# CONN.net
KiCad netlist of a schematic drawn in Altium Designer
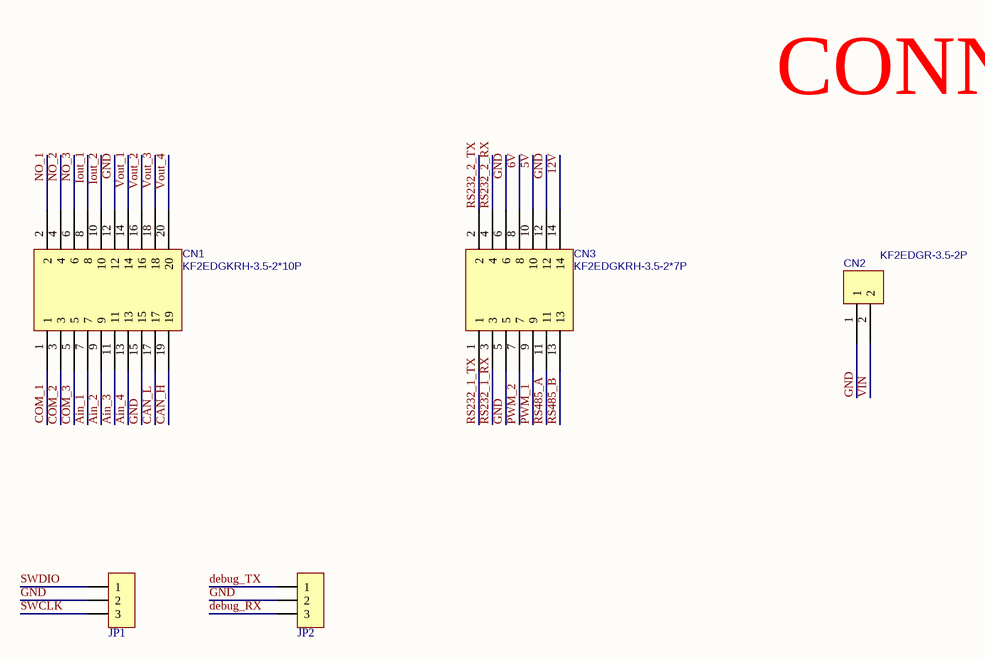
[diagram p0: CONN.SchDoc]

(export (version "E")
  (design (tool "Eeschema 10.0.6"))
  (components
    (comp (ref "CN1")
      (value "KF2EDGKRH-3.5-2*10P")
      (footprint "CONN-TH_20P-P3.50_KEFA_KF2EDGKRH-3.5-2X10P")
      (description "20P 间距P=3.5mm\r\n插拔式接线端子")
      (fields (field (name "BOM_SUPPLIER PART") "C2923169") (field (name "CONTRIBUTOR") "LCSC"))
      (libsource (lib "MICB") (part "KF2EDGKRH-3.5-2*10P"))
    )
    (comp (ref "CN2")
      (value "KF2EDGR-3.5-2P")
      (footprint "CONN-TH_P3.50_KF2EDGR-3.5-2P")
      (description "3.5mm 排数:1 每排P数:2 弯针\r\n插拔式接线端子")
      (fields (field (name "BOM_SUPPLIER PART") "C441171") (field (name "CONTRIBUTOR") "LCSC"))
      (libsource (lib "MICB") (part "KF2EDGR-3.5-2P"))
    )
    (comp (ref "CN3")
      (value "KF2EDGKRH-3.5-2*7P")
      (footprint "CONN-TH_14P-P3.50_KEFA_KF2EDGKRH-3.5-2X7P")
      (description "14P 间距P=3.5mm\r\n插拔式接线端子")
      (fields (field (name "BOM_SUPPLIER PART") "C2923166") (field (name "CONTRIBUTOR") "LCSC"))
      (libsource (lib "MICB") (part "KF2EDGKRH-3.5-2*7P"))
    )
    (comp (ref "JP1")
      (value "HDR-1X3")
      (footprint "HDR2.54-LI-3P")
      (description "3P排针")
      (fields (field (name "版权归属") "源创客"))
      (libsource (lib "接插件-脚距2.54") (part "Header 3"))
    )
    (comp (ref "JP2")
      (value "HDR-1X3")
      (footprint "HDR2.54-LI-3P")
      (description "3P排针")
      (fields (field (name "版权归属") "源创客"))
      (libsource (lib "接插件-脚距2.54") (part "Header 3"))
    )
  )
  (nets
    (net (code "1") (name "/5V") (class "Default")
      (node (ref "CN3") (pin "10") (pinfunction "10_10") (pintype "passive"))
    )
    (net (code "2") (name "/6V") (class "Default")
      (node (ref "CN3") (pin "8") (pinfunction "8_8") (pintype "passive"))
    )
    (net (code "3") (name "/12V") (class "Default")
      (node (ref "CN3") (pin "14") (pinfunction "14_14") (pintype "passive"))
    )
    (net (code "4") (name "/Ain_1") (class "Default")
      (node (ref "CN1") (pin "7") (pinfunction "7_7") (pintype "passive"))
    )
    (net (code "5") (name "/Ain_2") (class "Default")
      (node (ref "CN1") (pin "9") (pinfunction "9_9") (pintype "passive"))
    )
    (net (code "6") (name "/Ain_3") (class "Default")
      (node (ref "CN1") (pin "11") (pinfunction "11_11") (pintype "passive"))
    )
    (net (code "7") (name "/Ain_4") (class "Default")
      (node (ref "CN1") (pin "13") (pinfunction "13_13") (pintype "passive"))
    )
    (net (code "8") (name "/CAN_H") (class "Default")
      (node (ref "CN1") (pin "19") (pinfunction "19_19") (pintype "passive"))
    )
    (net (code "9") (name "/CAN_L") (class "Default")
      (node (ref "CN1") (pin "17") (pinfunction "17_17") (pintype "passive"))
    )
    (net (code "10") (name "/COM_1") (class "Default")
      (node (ref "CN1") (pin "1") (pinfunction "1_1") (pintype "passive"))
    )
    (net (code "11") (name "/COM_2") (class "Default")
      (node (ref "CN1") (pin "3") (pinfunction "3_3") (pintype "passive"))
    )
    (net (code "12") (name "/COM_3") (class "Default")
      (node (ref "CN1") (pin "5") (pinfunction "5_5") (pintype "passive"))
    )
    (net (code "13") (name "/GND") (class "Default")
      (node (ref "CN1") (pin "12") (pinfunction "12_12") (pintype "passive"))
      (node (ref "CN1") (pin "15") (pinfunction "15_15") (pintype "passive"))
      (node (ref "CN2") (pin "1") (pinfunction "1_1") (pintype "passive"))
      (node (ref "CN3") (pin "12") (pinfunction "12_12") (pintype "passive"))
      (node (ref "CN3") (pin "5") (pinfunction "5_5") (pintype "passive"))
      (node (ref "CN3") (pin "6") (pinfunction "6_6") (pintype "passive"))
      (node (ref "JP1") (pin "2") (pinfunction "2_2") (pintype "passive"))
      (node (ref "JP2") (pin "2") (pinfunction "2_2") (pintype "passive"))
    )
    (net (code "14") (name "/Iout_1") (class "Default")
      (node (ref "CN1") (pin "8") (pinfunction "8_8") (pintype "passive"))
    )
    (net (code "15") (name "/Iout_2") (class "Default")
      (node (ref "CN1") (pin "10") (pinfunction "10_10") (pintype "passive"))
    )
    (net (code "16") (name "/NO_1") (class "Default")
      (node (ref "CN1") (pin "2") (pinfunction "2_2") (pintype "passive"))
    )
    (net (code "17") (name "/NO_2") (class "Default")
      (node (ref "CN1") (pin "4") (pinfunction "4_4") (pintype "passive"))
    )
    (net (code "18") (name "/NO_3") (class "Default")
      (node (ref "CN1") (pin "6") (pinfunction "6_6") (pintype "passive"))
    )
    (net (code "19") (name "/PWM_1") (class "Default")
      (node (ref "CN3") (pin "9") (pinfunction "9_9") (pintype "passive"))
    )
    (net (code "20") (name "/PWM_2") (class "Default")
      (node (ref "CN3") (pin "7") (pinfunction "7_7") (pintype "passive"))
    )
    (net (code "21") (name "/RS232_1_RX") (class "Default")
      (node (ref "CN3") (pin "3") (pinfunction "3_3") (pintype "passive"))
    )
    (net (code "22") (name "/RS232_1_TX") (class "Default")
      (node (ref "CN3") (pin "1") (pinfunction "1_1") (pintype "passive"))
    )
    (net (code "23") (name "/RS232_2_RX") (class "Default")
      (node (ref "CN3") (pin "4") (pinfunction "4_4") (pintype "passive"))
    )
    (net (code "24") (name "/RS232_2_TX") (class "Default")
      (node (ref "CN3") (pin "2") (pinfunction "2_2") (pintype "passive"))
    )
    (net (code "25") (name "/RS485_A") (class "Default")
      (node (ref "CN3") (pin "11") (pinfunction "11_11") (pintype "passive"))
    )
    (net (code "26") (name "/RS485_B") (class "Default")
      (node (ref "CN3") (pin "13") (pinfunction "13_13") (pintype "passive"))
    )
    (net (code "27") (name "/SWCLK") (class "Default")
      (node (ref "JP1") (pin "3") (pinfunction "3_3") (pintype "passive"))
    )
    (net (code "28") (name "/SWDIO") (class "Default")
      (node (ref "JP1") (pin "1") (pinfunction "1_1") (pintype "passive"))
    )
    (net (code "29") (name "/VIN") (class "Default")
      (node (ref "CN2") (pin "2") (pinfunction "2_2") (pintype "passive"))
    )
    (net (code "30") (name "/Vout_1") (class "Default")
      (node (ref "CN1") (pin "14") (pinfunction "14_14") (pintype "passive"))
    )
    (net (code "31") (name "/Vout_2") (class "Default")
      (node (ref "CN1") (pin "16") (pinfunction "16_16") (pintype "passive"))
    )
    (net (code "32") (name "/Vout_3") (class "Default")
      (node (ref "CN1") (pin "18") (pinfunction "18_18") (pintype "passive"))
    )
    (net (code "33") (name "/Vout_4") (class "Default")
      (node (ref "CN1") (pin "20") (pinfunction "20_20") (pintype "passive"))
    )
    (net (code "34") (name "/debug_RX") (class "Default")
      (node (ref "JP2") (pin "3") (pinfunction "3_3") (pintype "passive"))
    )
    (net (code "35") (name "/debug_TX") (class "Default")
      (node (ref "JP2") (pin "1") (pinfunction "1_1") (pintype "passive"))
    )
  )
)
